# ADCS_breakout_Board_FinalVesion.net
KiCad netlist of a schematic drawn in Altium Designer
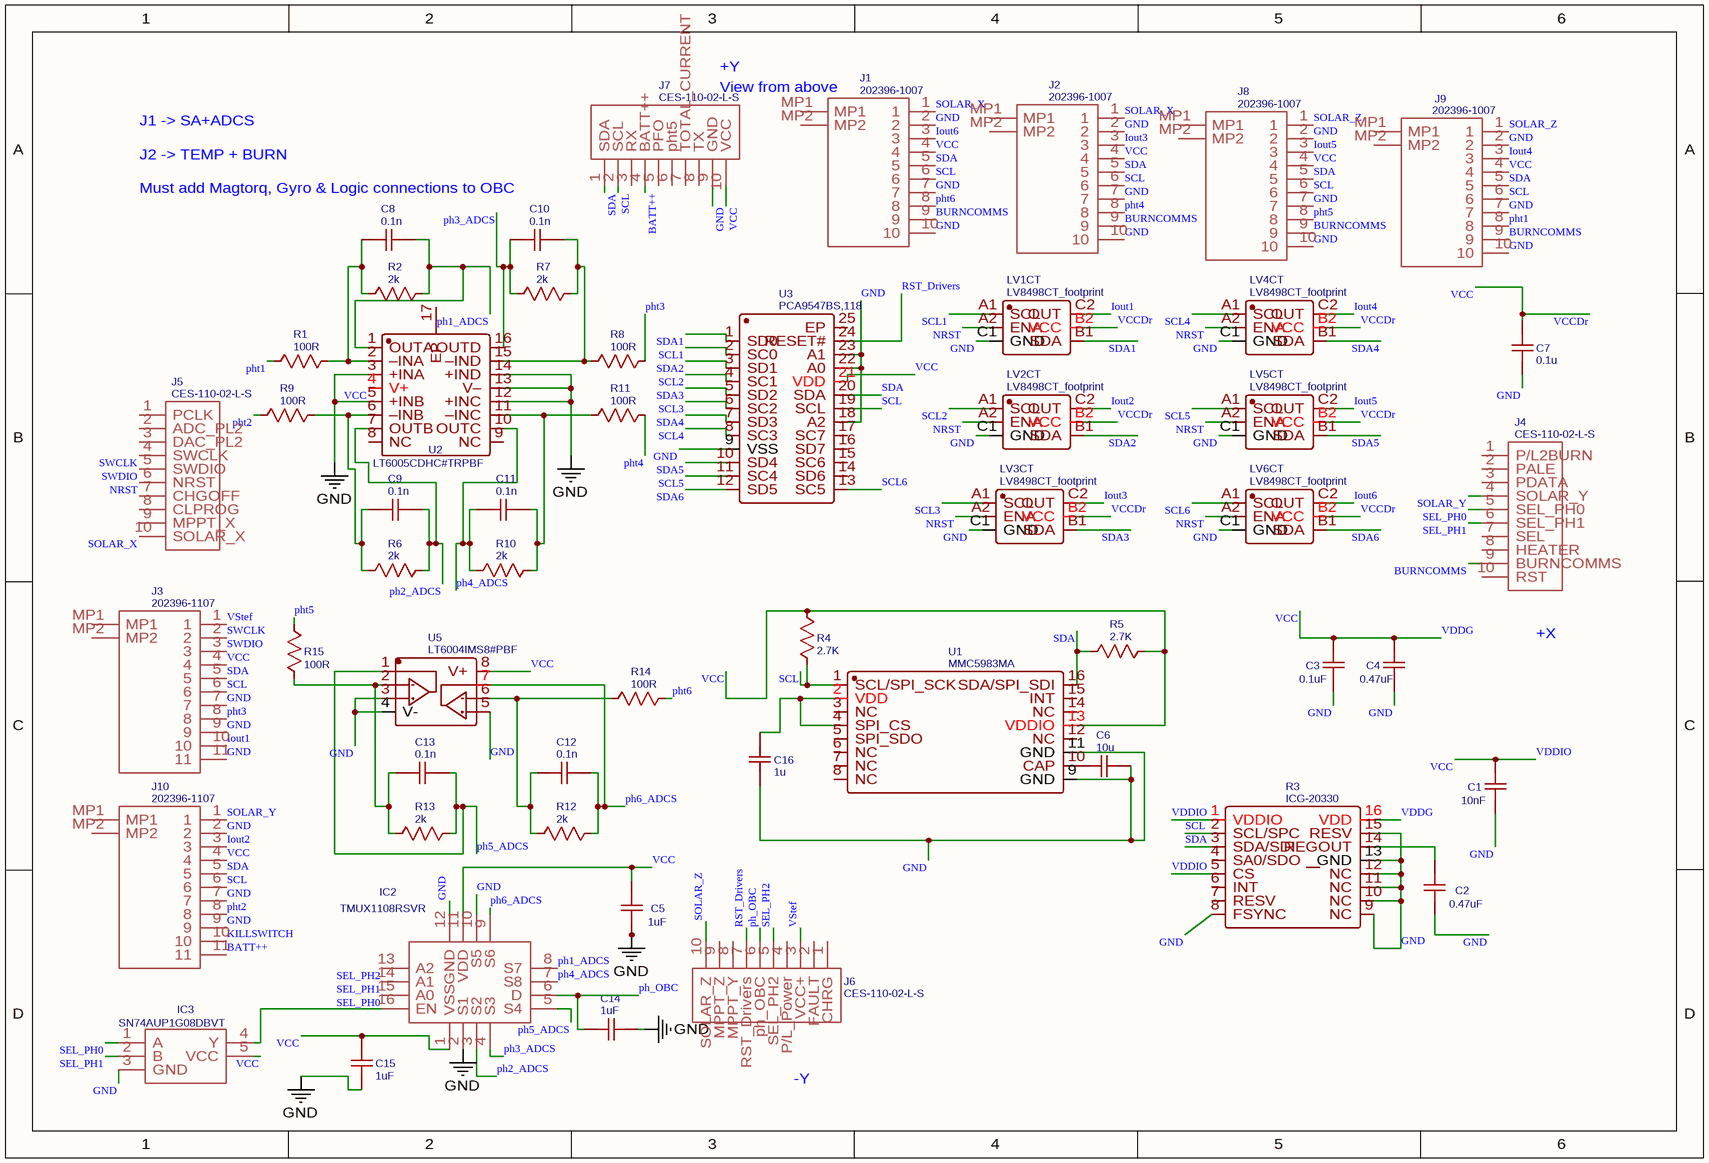
[diagram p0: ADCS&breakout_Board FinalVesion.schdoc]

(export (version "E")
  (design (tool "Eeschema 10.0.6"))
  (components
    (comp (ref "C1")
      (value "10nF")
      (footprint "C0603")
      (fields (field (name "CONTRIBUTOR") "LCEDA_Lib"))
      (libsource (lib "altium-import") (part "root_1_10nF_"))
    )
    (comp (ref "C2")
      (value "0.47uF")
      (footprint "C0603")
      (fields (field (name "CONTRIBUTOR") "LCEDA_Lib"))
      (libsource (lib "altium-import") (part "root_1_0.47uF_"))
    )
    (comp (ref "C3")
      (value "0.1uF")
      (footprint "C0603")
      (fields (field (name "CONTRIBUTOR") "LCEDA_Lib"))
      (libsource (lib "altium-import") (part "root_1_0.1uF_"))
    )
    (comp (ref "C4")
      (value "0.47uF")
      (footprint "C0603")
      (fields (field (name "CONTRIBUTOR") "LCEDA_Lib"))
      (libsource (lib "altium-import") (part "root_1_0.47uF_"))
    )
    (comp (ref "C5")
      (value "1uF")
      (footprint "C0603")
      (fields (field (name "CONTRIBUTOR") "LCEDA_Lib"))
      (libsource (lib "altium-import") (part "root_1_1uF_"))
    )
    (comp (ref "C6")
      (value "10u")
      (footprint "C0603")
      (fields (field (name "CONTRIBUTOR") "LCEDA_Lib"))
      (libsource (lib "altium-import") (part "root_0_10u_"))
    )
    (comp (ref "C7")
      (value "0.1u")
      (footprint "C0603")
      (fields (field (name "CONTRIBUTOR") "LCEDA_Lib"))
      (libsource (lib "altium-import") (part "root_3_0.1u_"))
    )
    (comp (ref "C8")
      (value "0.1n")
      (footprint "C0603")
      (fields (field (name "CONTRIBUTOR") "LCEDA_Lib"))
      (libsource (lib "altium-import") (part "root_0_0.1n_"))
    )
    (comp (ref "C9")
      (value "0.1n")
      (footprint "C0603")
      (fields (field (name "CONTRIBUTOR") "LCEDA_Lib"))
      (libsource (lib "altium-import") (part "root_0_0.1n_"))
    )
    (comp (ref "C10")
      (value "0.1n")
      (footprint "C0603")
      (fields (field (name "CONTRIBUTOR") "LCEDA_Lib"))
      (libsource (lib "altium-import") (part "root_0_0.1n_"))
    )
    (comp (ref "C11")
      (value "0.1n")
      (footprint "C0603")
      (fields (field (name "CONTRIBUTOR") "LCEDA_Lib"))
      (libsource (lib "altium-import") (part "root_0_0.1n_"))
    )
    (comp (ref "C12")
      (value "0.1n")
      (footprint "C0603")
      (fields (field (name "CONTRIBUTOR") "LCEDA_Lib"))
      (libsource (lib "altium-import") (part "root_0_0.1n_"))
    )
    (comp (ref "C13")
      (value "0.1n")
      (footprint "C0603")
      (fields (field (name "CONTRIBUTOR") "LCEDA_Lib"))
      (libsource (lib "altium-import") (part "root_0_0.1n_"))
    )
    (comp (ref "C14")
      (value "1uF")
      (footprint "C0603")
      (fields (field (name "CONTRIBUTOR") "LCEDA_Lib"))
      (libsource (lib "altium-import") (part "root_0_1uF_"))
    )
    (comp (ref "C15")
      (value "1uF")
      (footprint "C0603")
      (fields (field (name "CONTRIBUTOR") "LCEDA_Lib"))
      (libsource (lib "altium-import") (part "root_3_1uF_"))
    )
    (comp (ref "C16")
      (value "1u")
      (footprint "C0603")
      (fields (field (name "CONTRIBUTOR") "LCEDA_Lib"))
      (libsource (lib "altium-import") (part "root_3_1u_"))
    )
    (comp (ref "IC2")
      (value "TMUX1108RSVR")
      (footprint "QFN40P180X260X55-16N")
      (fields (field (name "CONTRIBUTOR") "Pol Gimenez"))
      (libsource (lib "altium-import") (part "root_1_TMUX1108RSVR_"))
    )
    (comp (ref "IC3")
      (value "SN74AUP1G08DBVT")
      (footprint "SOT95P280X145-5N")
      (fields (field (name "CONTRIBUTOR") "Pol Gimenez"))
      (libsource (lib "altium-import") (part "root_0_SN74AUP1G08DBVT_"))
    )
    (comp (ref "J1")
      (value "202396-1007")
      (footprint "2023961007")
      (fields (field (name "CONTRIBUTOR") "Pol Gimenez"))
      (libsource (lib "altium-import") (part "root_0_202396-1007_"))
    )
    (comp (ref "J2")
      (value "202396-1007")
      (footprint "2023961007")
      (fields (field (name "CONTRIBUTOR") "Pol Gimenez"))
      (libsource (lib "altium-import") (part "root_0_202396-1007_"))
    )
    (comp (ref "J3")
      (value "202396-1107")
      (footprint "2023961107")
      (fields (field (name "CONTRIBUTOR") "Pol Gimenez"))
      (libsource (lib "altium-import") (part "root_0_202396-1107_"))
    )
    (comp (ref "J4")
      (value "CES-110-02-L-S")
      (footprint "CES-110-XX-Y-S")
      (fields (field (name "CONTRIBUTOR") "George-vlad Enache"))
      (libsource (lib "altium-import") (part "root_0_CES-110-02-L-S_"))
    )
    (comp (ref "J5")
      (value "CES-110-02-L-S")
      (footprint "CES-110-XX-Y-S")
      (fields (field (name "CONTRIBUTOR") "George-vlad Enache"))
      (libsource (lib "altium-import") (part "root_0_CES-110-02-L-S_"))
    )
    (comp (ref "J6")
      (value "CES-110-02-L-S")
      (footprint "CES-110-XX-Y-S")
      (fields (field (name "CONTRIBUTOR") "George-vlad Enache"))
      (libsource (lib "altium-import") (part "root_3_CES-110-02-L-S_"))
    )
    (comp (ref "J7")
      (value "CES-110-02-L-S")
      (footprint "CES-110-XX-Y-S")
      (fields (field (name "CONTRIBUTOR") "George-vlad Enache"))
      (libsource (lib "altium-import") (part "root_1_CES-110-02-L-S_"))
    )
    (comp (ref "J8")
      (value "202396-1007")
      (footprint "2023961007")
      (fields (field (name "CONTRIBUTOR") "Pol Gimenez"))
      (libsource (lib "altium-import") (part "root_0_202396-1007_"))
    )
    (comp (ref "J9")
      (value "202396-1007")
      (footprint "2023961007")
      (fields (field (name "CONTRIBUTOR") "Pol Gimenez"))
      (libsource (lib "altium-import") (part "root_0_202396-1007_"))
    )
    (comp (ref "J10")
      (value "202396-1107")
      (footprint "2023961107")
      (fields (field (name "CONTRIBUTOR") "Pol Gimenez"))
      (libsource (lib "altium-import") (part "root_0_202396-1107_"))
    )
    (comp (ref "LV1CT")
      (value "LV8498CT_footprint")
      (footprint "WLP-6_L1.30-W0.90-P0.40-TL")
      (fields
        (field (name "BOM_MANUFACTURER PART") "LV8498CT-TE-L-H")
        (field (name "BOM_SUPPLIER PART") "863-LV8498CT-TE-L-H")
        (field (name "CONTRIBUTOR") "Miguel Diaz Montiel")
      )
      (libsource (lib "altium-import") (part "root_0_LV8498CT_footprint_"))
    )
    (comp (ref "LV2CT")
      (value "LV8498CT_footprint")
      (footprint "WLP-6_L1.30-W0.90-P0.40-TL")
      (fields
        (field (name "BOM_MANUFACTURER PART") "LV8498CT-TE-L-H")
        (field (name "BOM_SUPPLIER PART") "863-LV8498CT-TE-L-H")
        (field (name "CONTRIBUTOR") "Miguel Diaz Montiel")
      )
      (libsource (lib "altium-import") (part "root_0_LV8498CT_footprint_"))
    )
    (comp (ref "LV3CT")
      (value "LV8498CT_footprint")
      (footprint "WLP-6_L1.30-W0.90-P0.40-TL")
      (fields
        (field (name "BOM_MANUFACTURER PART") "LV8498CT-TE-L-H")
        (field (name "BOM_SUPPLIER PART") "863-LV8498CT-TE-L-H")
        (field (name "CONTRIBUTOR") "Miguel Diaz Montiel")
      )
      (libsource (lib "altium-import") (part "root_0_LV8498CT_footprint_"))
    )
    (comp (ref "LV4CT")
      (value "LV8498CT_footprint")
      (footprint "WLP-6_L1.30-W0.90-P0.40-TL")
      (fields
        (field (name "BOM_MANUFACTURER PART") "LV8498CT-TE-L-H")
        (field (name "BOM_SUPPLIER PART") "863-LV8498CT-TE-L-H")
        (field (name "CONTRIBUTOR") "Miguel Diaz Montiel")
      )
      (libsource (lib "altium-import") (part "root_0_LV8498CT_footprint_"))
    )
    (comp (ref "LV5CT")
      (value "LV8498CT_footprint")
      (footprint "WLP-6_L1.30-W0.90-P0.40-TL")
      (fields
        (field (name "BOM_MANUFACTURER PART") "LV8498CT-TE-L-H")
        (field (name "BOM_SUPPLIER PART") "863-LV8498CT-TE-L-H")
        (field (name "CONTRIBUTOR") "Miguel Diaz Montiel")
      )
      (libsource (lib "altium-import") (part "root_0_LV8498CT_footprint_"))
    )
    (comp (ref "LV6CT")
      (value "LV8498CT_footprint")
      (footprint "WLP-6_L1.30-W0.90-P0.40-TL")
      (fields
        (field (name "BOM_MANUFACTURER PART") "LV8498CT-TE-L-H")
        (field (name "BOM_SUPPLIER PART") "863-LV8498CT-TE-L-H")
        (field (name "CONTRIBUTOR") "Miguel Diaz Montiel")
      )
      (libsource (lib "altium-import") (part "root_0_LV8498CT_footprint_"))
    )
    (comp (ref "R1")
      (value "100R")
      (footprint "R0603")
      (fields (field (name "CONTRIBUTOR") "LCEDA_Lib"))
      (libsource (lib "altium-import") (part "root_0_100R_"))
    )
    (comp (ref "R2")
      (value "2k")
      (footprint "R0603")
      (fields (field (name "CONTRIBUTOR") "LCEDA_Lib"))
      (libsource (lib "altium-import") (part "root_2_2k_"))
    )
    (comp (ref "R3")
      (value "ICG-20330")
      (footprint "LGA-16_L3.0-W3.0-P0.50-BL")
      (fields (field (name "BOM_SUPPLIER PART") "C2655094") (field (name "CONTRIBUTOR") "LCSC"))
      (libsource (lib "altium-import") (part "root_0_ICG-20330_"))
    )
    (comp (ref "R4")
      (value "2.7K")
      (footprint "R0603")
      (fields (field (name "CONTRIBUTOR") "LCEDA_Lib"))
      (libsource (lib "altium-import") (part "root_1_2.7K_"))
    )
    (comp (ref "R5")
      (value "2.7K")
      (footprint "R0603")
      (fields (field (name "CONTRIBUTOR") "LCEDA_Lib"))
      (libsource (lib "altium-import") (part "root_2_2.7K_"))
    )
    (comp (ref "R6")
      (value "2k")
      (footprint "R0603")
      (fields (field (name "CONTRIBUTOR") "LCEDA_Lib"))
      (libsource (lib "altium-import") (part "root_2_2k_"))
    )
    (comp (ref "R7")
      (value "2k")
      (footprint "R0603")
      (fields (field (name "CONTRIBUTOR") "LCEDA_Lib"))
      (libsource (lib "altium-import") (part "root_2_2k_"))
    )
    (comp (ref "R8")
      (value "100R")
      (footprint "R0603")
      (fields (field (name "CONTRIBUTOR") "LCEDA_Lib"))
      (libsource (lib "altium-import") (part "root_0_100R_"))
    )
    (comp (ref "R9")
      (value "100R")
      (footprint "R0603")
      (fields (field (name "CONTRIBUTOR") "LCEDA_Lib"))
      (libsource (lib "altium-import") (part "root_0_100R_"))
    )
    (comp (ref "R10")
      (value "2k")
      (footprint "R0603")
      (fields (field (name "CONTRIBUTOR") "LCEDA_Lib"))
      (libsource (lib "altium-import") (part "root_2_2k_"))
    )
    (comp (ref "R11")
      (value "100R")
      (footprint "R0603")
      (fields (field (name "CONTRIBUTOR") "LCEDA_Lib"))
      (libsource (lib "altium-import") (part "root_0_100R_"))
    )
    (comp (ref "R12")
      (value "2k")
      (footprint "R0603")
      (fields (field (name "CONTRIBUTOR") "LCEDA_Lib"))
      (libsource (lib "altium-import") (part "root_2_2k_"))
    )
    (comp (ref "R13")
      (value "2k")
      (footprint "R0603")
      (fields (field (name "CONTRIBUTOR") "LCEDA_Lib"))
      (libsource (lib "altium-import") (part "root_2_2k_"))
    )
    (comp (ref "R14")
      (value "100R")
      (footprint "R0603")
      (fields (field (name "CONTRIBUTOR") "LCEDA_Lib"))
      (libsource (lib "altium-import") (part "root_0_100R_"))
    )
    (comp (ref "R15")
      (value "100R")
      (footprint "R0603")
      (fields (field (name "CONTRIBUTOR") "LCEDA_Lib"))
      (libsource (lib "altium-import") (part "root_1_100R_"))
    )
    (comp (ref "U1")
      (value "MMC5983MA")
      (footprint "LGA-16_L3.0-W3.0-P0.50-BL_SQ")
      (fields (field (name "BOM_SUPPLIER PART") "C404329") (field (name "CONTRIBUTOR") "LCSC"))
      (libsource (lib "altium-import") (part "root_0_MMC5983MA_"))
    )
    (comp (ref "U2")
      (value "LT6005CDHC#TRPBF")
      (footprint "DFN-16_L5.0-W3.0-P0.50-BL-EP")
      (fields (field (name "BOM_SUPPLIER PART") "C672687") (field (name "CONTRIBUTOR") "LCSC"))
      (libsource (lib "altium-import") (part "root_0_LT6005CDHC#TRPBF_"))
    )
    (comp (ref "U3")
      (value "PCA9547BS,118")
      (footprint "HVQFN-24_L4.0-W4.0-P0.50-BL-EP2.1")
      (fields (field (name "BOM_SUPPLIER PART") "C2652947") (field (name "CONTRIBUTOR") "LCSC"))
      (libsource (lib "altium-import") (part "root_0_PCA9547BS,118_"))
    )
    (comp (ref "U5")
      (value "LT6004IMS8#PBF")
      (footprint "MOSP-8_L3.0-W3.0-P0.65-LS4.9-BL")
      (fields (field (name "BOM_SUPPLIER PART") "C117424") (field (name "CONTRIBUTOR") "LCSC"))
      (libsource (lib "altium-import") (part "root_0_LT6004IMS8#PBF_"))
    )
  )
  (nets
    (net (code "1") (name "/BATT++") (class "Default")
      (node (ref "J10") (pin "11") (pinfunction "11_11") (pintype "passive"))
      (node (ref "J7") (pin "4") (pinfunction "BATT++_4") (pintype "passive"))
    )
    (net (code "2") (name "/BURNCOMMS") (class "Default")
      (node (ref "J1") (pin "9") (pinfunction "9_9") (pintype "passive"))
      (node (ref "J2") (pin "9") (pinfunction "9_9") (pintype "passive"))
      (node (ref "J4") (pin "9") (pinfunction "MPPT_X_9") (pintype "passive"))
      (node (ref "J8") (pin "9") (pinfunction "9_9") (pintype "passive"))
      (node (ref "J9") (pin "9") (pinfunction "9_9") (pintype "passive"))
    )
    (net (code "3") (name "/Iout1") (class "Default")
      (node (ref "J3") (pin "10") (pinfunction "10_10") (pintype "passive"))
      (node (ref "LV1CT") (pin "C2") (pinfunction "OUT_C2") (pintype "passive"))
    )
    (net (code "4") (name "/Iout2") (class "Default")
      (node (ref "J10") (pin "3") (pinfunction "3_3") (pintype "passive"))
      (node (ref "LV2CT") (pin "C2") (pinfunction "OUT_C2") (pintype "passive"))
    )
    (net (code "5") (name "/Iout3") (class "Default")
      (node (ref "J2") (pin "3") (pinfunction "3_3") (pintype "passive"))
      (node (ref "LV3CT") (pin "C2") (pinfunction "OUT_C2") (pintype "passive"))
    )
    (net (code "6") (name "/Iout4") (class "Default")
      (node (ref "J9") (pin "3") (pinfunction "3_3") (pintype "passive"))
      (node (ref "LV4CT") (pin "C2") (pinfunction "OUT_C2") (pintype "passive"))
    )
    (net (code "7") (name "/Iout5") (class "Default")
      (node (ref "J8") (pin "3") (pinfunction "3_3") (pintype "passive"))
      (node (ref "LV5CT") (pin "C2") (pinfunction "OUT_C2") (pintype "passive"))
    )
    (net (code "8") (name "/Iout6") (class "Default")
      (node (ref "J1") (pin "3") (pinfunction "3_3") (pintype "passive"))
      (node (ref "LV6CT") (pin "C2") (pinfunction "OUT_C2") (pintype "passive"))
    )
    (net (code "9") (name "/KILLSWITCH") (class "Default")
      (node (ref "J10") (pin "10") (pinfunction "10_10") (pintype "passive"))
    )
    (net (code "10") (name "/NRST") (class "Default")
      (node (ref "J5") (pin "6") (pinfunction "NRST_6") (pintype "passive"))
      (node (ref "LV1CT") (pin "A2") (pinfunction "ENA_A2") (pintype "passive"))
      (node (ref "LV2CT") (pin "A2") (pinfunction "ENA_A2") (pintype "passive"))
      (node (ref "LV3CT") (pin "A2") (pinfunction "ENA_A2") (pintype "passive"))
      (node (ref "LV4CT") (pin "A2") (pinfunction "ENA_A2") (pintype "passive"))
      (node (ref "LV5CT") (pin "A2") (pinfunction "ENA_A2") (pintype "passive"))
      (node (ref "LV6CT") (pin "A2") (pinfunction "ENA_A2") (pintype "passive"))
    )
    (net (code "11") (name "/RST_Drivers") (class "Default")
      (node (ref "J6") (pin "7") (pinfunction "RST_Drivers_7") (pintype "passive"))
      (node (ref "U3") (pin "24") (pinfunction "RESET#_24") (pintype "passive"))
    )
    (net (code "12") (name "/SCL") (class "Default")
      (node (ref "J1") (pin "6") (pinfunction "6_6") (pintype "passive"))
      (node (ref "J10") (pin "6") (pinfunction "6_6") (pintype "passive"))
      (node (ref "J2") (pin "6") (pinfunction "6_6") (pintype "passive"))
      (node (ref "J3") (pin "6") (pinfunction "6_6") (pintype "passive"))
      (node (ref "J7") (pin "2") (pinfunction "SCL_2") (pintype "passive"))
      (node (ref "J8") (pin "6") (pinfunction "6_6") (pintype "passive"))
      (node (ref "J9") (pin "6") (pinfunction "6_6") (pintype "passive"))
      (node (ref "R3") (pin "2") (pinfunction "SCL/SPC_2") (pintype "passive"))
      (node (ref "R4") (pin "1") (pinfunction "1_1") (pintype "passive"))
      (node (ref "U1") (pin "1") (pinfunction "SCL/SPI_SCK_1") (pintype "passive"))
      (node (ref "U3") (pin "19") (pinfunction "SCL_19") (pintype "passive"))
    )
    (net (code "13") (name "/SCL1") (class "Default")
      (node (ref "LV1CT") (pin "A1") (pinfunction "SCL_A1") (pintype "passive"))
      (node (ref "U3") (pin "2") (pinfunction "SC0_2") (pintype "passive"))
    )
    (net (code "14") (name "/SCL2") (class "Default")
      (node (ref "LV2CT") (pin "A1") (pinfunction "SCL_A1") (pintype "passive"))
      (node (ref "U3") (pin "4") (pinfunction "SC1_4") (pintype "passive"))
    )
    (net (code "15") (name "/SCL3") (class "Default")
      (node (ref "LV3CT") (pin "A1") (pinfunction "SCL_A1") (pintype "passive"))
      (node (ref "U3") (pin "6") (pinfunction "SC2_6") (pintype "passive"))
    )
    (net (code "16") (name "/SCL4") (class "Default")
      (node (ref "LV4CT") (pin "A1") (pinfunction "SCL_A1") (pintype "passive"))
      (node (ref "U3") (pin "8") (pinfunction "SC3_8") (pintype "passive"))
    )
    (net (code "17") (name "/SCL5") (class "Default")
      (node (ref "LV5CT") (pin "A1") (pinfunction "SCL_A1") (pintype "passive"))
      (node (ref "U3") (pin "11") (pinfunction "SC4_11") (pintype "passive"))
    )
    (net (code "18") (name "/SCL6") (class "Default")
      (node (ref "LV6CT") (pin "A1") (pinfunction "SCL_A1") (pintype "passive"))
      (node (ref "U3") (pin "13") (pinfunction "SC5_13") (pintype "passive"))
    )
    (net (code "19") (name "/SDA") (class "Default")
      (node (ref "J1") (pin "5") (pinfunction "5_5") (pintype "passive"))
      (node (ref "J10") (pin "5") (pinfunction "5_5") (pintype "passive"))
      (node (ref "J2") (pin "5") (pinfunction "5_5") (pintype "passive"))
      (node (ref "J3") (pin "5") (pinfunction "5_5") (pintype "passive"))
      (node (ref "J7") (pin "1") (pinfunction "SDA_1") (pintype "passive"))
      (node (ref "J8") (pin "5") (pinfunction "5_5") (pintype "passive"))
      (node (ref "J9") (pin "5") (pinfunction "5_5") (pintype "passive"))
      (node (ref "R3") (pin "3") (pinfunction "SDA/SDI_3") (pintype "passive"))
      (node (ref "R5") (pin "2") (pinfunction "2_2") (pintype "passive"))
      (node (ref "U1") (pin "16") (pinfunction "SDA/SPI_SDI_16") (pintype "passive"))
      (node (ref "U3") (pin "20") (pinfunction "SDA_20") (pintype "passive"))
    )
    (net (code "20") (name "/SDA1") (class "Default")
      (node (ref "LV1CT") (pin "B1") (pinfunction "SDA_B1") (pintype "passive"))
      (node (ref "U3") (pin "1") (pinfunction "SD0_1") (pintype "passive"))
    )
    (net (code "21") (name "/SDA2") (class "Default")
      (node (ref "LV2CT") (pin "B1") (pinfunction "SDA_B1") (pintype "passive"))
      (node (ref "U3") (pin "3") (pinfunction "SD1_3") (pintype "passive"))
    )
    (net (code "22") (name "/SDA3") (class "Default")
      (node (ref "LV3CT") (pin "B1") (pinfunction "SDA_B1") (pintype "passive"))
      (node (ref "U3") (pin "5") (pinfunction "SD2_5") (pintype "passive"))
    )
    (net (code "23") (name "/SDA4") (class "Default")
      (node (ref "LV4CT") (pin "B1") (pinfunction "SDA_B1") (pintype "passive"))
      (node (ref "U3") (pin "7") (pinfunction "SD3_7") (pintype "passive"))
    )
    (net (code "24") (name "/SDA5") (class "Default")
      (node (ref "LV5CT") (pin "B1") (pinfunction "SDA_B1") (pintype "passive"))
      (node (ref "U3") (pin "10") (pinfunction "SD4_10") (pintype "passive"))
    )
    (net (code "25") (name "/SDA6") (class "Default")
      (node (ref "LV6CT") (pin "B1") (pinfunction "SDA_B1") (pintype "passive"))
      (node (ref "U3") (pin "12") (pinfunction "SD5_12") (pintype "passive"))
    )
    (net (code "26") (name "/SEL_PH0") (class "Default")
      (node (ref "IC2") (pin "15") (pinfunction "A0_15") (pintype "passive"))
      (node (ref "IC3") (pin "1") (pinfunction "A_1") (pintype "passive"))
      (node (ref "J4") (pin "5") (pinfunction "SWDIO_5") (pintype "passive"))
    )
    (net (code "27") (name "/SEL_PH1") (class "Default")
      (node (ref "IC2") (pin "14") (pinfunction "A1_14") (pintype "passive"))
      (node (ref "IC3") (pin "2") (pinfunction "B_2") (pintype "passive"))
      (node (ref "J4") (pin "6") (pinfunction "NRST_6") (pintype "passive"))
    )
    (net (code "28") (name "/SEL_PH2") (class "Default")
      (node (ref "IC2") (pin "13") (pinfunction "A2_13") (pintype "passive"))
      (node (ref "J6") (pin "5") (pinfunction "SEL_PH2_5") (pintype "passive"))
    )
    (net (code "29") (name "/SOLAR_X") (class "Default")
      (node (ref "J1") (pin "1") (pinfunction "1_1") (pintype "passive"))
      (node (ref "J2") (pin "1") (pinfunction "1_1") (pintype "passive"))
      (node (ref "J5") (pin "10") (pinfunction "SOLAR_X_10") (pintype "passive"))
    )
    (net (code "30") (name "/SOLAR_Y") (class "Default")
      (node (ref "J10") (pin "1") (pinfunction "1_1") (pintype "passive"))
      (node (ref "J4") (pin "4") (pinfunction "SWCLK_4") (pintype "passive"))
    )
    (net (code "31") (name "/SOLAR_Z") (class "Default")
      (node (ref "J6") (pin "10") (pinfunction "SOLAR_Z_10") (pintype "passive"))
      (node (ref "J8") (pin "1") (pinfunction "1_1") (pintype "passive"))
      (node (ref "J9") (pin "1") (pinfunction "1_1") (pintype "passive"))
    )
    (net (code "32") (name "/SWCLK") (class "Default")
      (node (ref "J3") (pin "2") (pinfunction "2_2") (pintype "passive"))
      (node (ref "J5") (pin "4") (pinfunction "SWCLK_4") (pintype "passive"))
    )
    (net (code "33") (name "/SWDIO") (class "Default")
      (node (ref "J3") (pin "3") (pinfunction "3_3") (pintype "passive"))
      (node (ref "J5") (pin "5") (pinfunction "SWDIO_5") (pintype "passive"))
    )
    (net (code "34") (name "/VCC") (class "Default")
      (node (ref "C1") (pin "2") (pinfunction "2_2") (pintype "passive"))
      (node (ref "C15") (pin "1") (pinfunction "1_1") (pintype "passive"))
      (node (ref "C3") (pin "2") (pinfunction "2_2") (pintype "passive"))
      (node (ref "C4") (pin "2") (pinfunction "2_2") (pintype "passive"))
      (node (ref "C5") (pin "2") (pinfunction "2_2") (pintype "passive"))
      (node (ref "C7") (pin "1") (pinfunction "1_1") (pintype "passive"))
      (node (ref "IC2") (pin "1") (pinfunction "VSS_1") (pintype "passive"))
      (node (ref "IC2") (pin "11") (pinfunction "VDD_11") (pintype "passive"))
      (node (ref "IC3") (pin "5") (pinfunction "VCC_5") (pintype "passive"))
      (node (ref "J1") (pin "4") (pinfunction "4_4") (pintype "passive"))
      (node (ref "J10") (pin "4") (pinfunction "4_4") (pintype "passive"))
      (node (ref "J2") (pin "4") (pinfunction "4_4") (pintype "passive"))
      (node (ref "J3") (pin "4") (pinfunction "4_4") (pintype "passive"))
      (node (ref "J7") (pin "10") (pinfunction "VCC_10") (pintype "passive"))
      (node (ref "J8") (pin "4") (pinfunction "4_4") (pintype "passive"))
      (node (ref "J9") (pin "4") (pinfunction "4_4") (pintype "passive"))
      (node (ref "LV1CT") (pin "B2") (pinfunction "VCC_B2") (pintype "passive"))
      (node (ref "LV2CT") (pin "B2") (pinfunction "VCC_B2") (pintype "passive"))
      (node (ref "LV3CT") (pin "B2") (pinfunction "VCC_B2") (pintype "passive"))
      (node (ref "LV4CT") (pin "B2") (pinfunction "VCC_B2") (pintype "passive"))
      (node (ref "LV5CT") (pin "B2") (pinfunction "VCC_B2") (pintype "passive"))
      (node (ref "LV6CT") (pin "B2") (pinfunction "VCC_B2") (pintype "passive"))
      (node (ref "R3") (pin "1") (pinfunction "VDDIO_1") (pintype "passive"))
      (node (ref "R3") (pin "16") (pinfunction "VDD_16") (pintype "passive"))
      (node (ref "R3") (pin "5") (pinfunction "CS_5") (pintype "passive"))
      (node (ref "R4") (pin "2") (pinfunction "2_2") (pintype "passive"))
      (node (ref "R5") (pin "1") (pinfunction "1_1") (pintype "passive"))
      (node (ref "U1") (pin "13") (pinfunction "VDDIO_13") (pintype "passive"))
      (node (ref "U2") (pin "4") (pinfunction "V+_4") (pintype "passive"))
      (node (ref "U3") (pin "21") (pinfunction "VDD_21") (pintype "passive"))
      (node (ref "U5") (pin "8") (pinfunction "V+_8") (pintype "passive"))
    )
    (net (code "35") (name "/VStef") (class "Default")
      (node (ref "J3") (pin "1") (pinfunction "1_1") (pintype "passive"))
      (node (ref "J6") (pin "3") (pinfunction "VCC+_3") (pintype "passive"))
    )
    (net (code "36") (name "/ph1_ADCS") (class "Default")
      (node (ref "C8") (pin "2") (pinfunction "2_2") (pintype "passive"))
      (node (ref "IC2") (pin "8") (pinfunction "S7_8") (pintype "passive"))
      (node (ref "R2") (pin "1") (pinfunction "1_1") (pintype "passive"))
      (node (ref "U2") (pin "1") (pinfunction "OUTA_1") (pintype "passive"))
    )
    (net (code "37") (name "/ph2_ADCS") (class "Default")
      (node (ref "C9") (pin "2") (pinfunction "2_2") (pintype "passive"))
      (node (ref "IC2") (pin "3") (pinfunction "S2_3") (pintype "passive"))
      (node (ref "R6") (pin "1") (pinfunction "1_1") (pintype "passive"))
      (node (ref "U2") (pin "7") (pinfunction "OUTB_7") (pintype "passive"))
    )
    (net (code "38") (name "/ph3_ADCS") (class "Default")
      (node (ref "C10") (pin "1") (pinfunction "1_1") (pintype "passive"))
      (node (ref "IC2") (pin "4") (pinfunction "S3_4") (pintype "passive"))
      (node (ref "R7") (pin "2") (pinfunction "2_2") (pintype "passive"))
      (node (ref "U2") (pin "16") (pinfunction "OUTD_16") (pintype "passive"))
    )
    (net (code "39") (name "/ph4_ADCS") (class "Default")
      (node (ref "C11") (pin "1") (pinfunction "1_1") (pintype "passive"))
      (node (ref "IC2") (pin "7") (pinfunction "S8_7") (pintype "passive"))
      (node (ref "R10") (pin "2") (pinfunction "2_2") (pintype "passive"))
      (node (ref "U2") (pin "10") (pinfunction "OUTC_10") (pintype "passive"))
    )
    (net (code "40") (name "/ph5_ADCS") (class "Default")
      (node (ref "C13") (pin "2") (pinfunction "2_2") (pintype "passive"))
      (node (ref "IC2") (pin "5") (pinfunction "S4_5") (pintype "passive"))
      (node (ref "R13") (pin "1") (pinfunction "1_1") (pintype "passive"))
      (node (ref "U5") (pin "1") (pinfunction "OUTA_1") (pintype "passive"))
    )
    (net (code "41") (name "/ph6_ADCS") (class "Default")
      (node (ref "C12") (pin "2") (pinfunction "2_2") (pintype "passive"))
      (node (ref "IC2") (pin "9") (pinfunction "S6_9") (pintype "passive"))
      (node (ref "R12") (pin "1") (pinfunction "1_1") (pintype "passive"))
      (node (ref "U5") (pin "7") (pinfunction "OUTB_7") (pintype "passive"))
    )
    (net (code "42") (name "/ph_OBC") (class "Default")
      (node (ref "C14") (pin "1") (pinfunction "1_1") (pintype "passive"))
      (node (ref "IC2") (pin "6") (pinfunction "D_6") (pintype "passive"))
      (node (ref "J6") (pin "6") (pinfunction "ph_OBC_6") (pintype "passive"))
    )
    (net (code "43") (name "/pht1") (class "Default")
      (node (ref "J9") (pin "8") (pinfunction "8_8") (pintype "passive"))
      (node (ref "R1") (pin "1") (pinfunction "1_1") (pintype "passive"))
    )
    (net (code "44") (name "/pht2") (class "Default")
      (node (ref "J10") (pin "8") (pinfunction "8_8") (pintype "passive"))
      (node (ref "R9") (pin "1") (pinfunction "1_1") (pintype "passive"))
    )
    (net (code "45") (name "/pht3") (class "Default")
      (node (ref "J3") (pin "8") (pinfunction "8_8") (pintype "passive"))
      (node (ref "R8") (pin "2") (pinfunction "2_2") (pintype "passive"))
    )
    (net (code "46") (name "/pht4") (class "Default")
      (node (ref "J2") (pin "8") (pinfunction "8_8") (pintype "passive"))
      (node (ref "R11") (pin "2") (pinfunction "2_2") (pintype "passive"))
    )
    (net (code "47") (name "/pht5") (class "Default")
      (node (ref "J8") (pin "8") (pinfunction "8_8") (pintype "passive"))
      (node (ref "R15") (pin "2") (pinfunction "2_2") (pintype "passive"))
    )
    (net (code "48") (name "/pht6") (class "Default")
      (node (ref "J1") (pin "8") (pinfunction "8_8") (pintype "passive"))
      (node (ref "R14") (pin "2") (pinfunction "2_2") (pintype "passive"))
    )
    (net (code "49") (name "GND") (class "Default")
      (node (ref "C1") (pin "1") (pinfunction "1_1") (pintype "passive"))
      (node (ref "C14") (pin "2") (pinfunction "2_2") (pintype "passive"))
      (node (ref "C15") (pin "2") (pinfunction "2_2") (pintype "passive"))
      (node (ref "C16") (pin "2") (pinfunction "2_2") (pintype "passive"))
      (node (ref "C2") (pin "1") (pinfunction "1_1") (pintype "passive"))
      (node (ref "C3") (pin "1") (pinfunction "1_1") (pintype "passive"))
      (node (ref "C4") (pin "1") (pinfunction "1_1") (pintype "passive"))
      (node (ref "C5") (pin "1") (pinfunction "1_1") (pintype "passive"))
      (node (ref "C6") (pin "2") (pinfunction "2_2") (pintype "passive"))
      (node (ref "C7") (pin "2") (pinfunction "2_2") (pintype "passive"))
      (node (ref "IC2") (pin "10") (pinfunction "S5_10") (pintype "passive"))
      (node (ref "IC2") (pin "12") (pinfunction "GND_12") (pintype "passive"))
      (node (ref "IC2") (pin "2") (pinfunction "S1_2") (pintype "passive"))
      (node (ref "IC3") (pin "3") (pinfunction "GND_3") (pintype "passive"))
      (node (ref "J1") (pin "10") (pinfunction "10_10") (pintype "passive"))
      (node (ref "J1") (pin "2") (pinfunction "2_2") (pintype "passive"))
      (node (ref "J1") (pin "7") (pinfunction "7_7") (pintype "passive"))
      (node (ref "J10") (pin "2") (pinfunction "2_2") (pintype "passive"))
      (node (ref "J10") (pin "7") (pinfunction "7_7") (pintype "passive"))
      (node (ref "J10") (pin "9") (pinfunction "9_9") (pintype "passive"))
      (node (ref "J2") (pin "10") (pinfunction "10_10") (pintype "passive"))
      (node (ref "J2") (pin "2") (pinfunction "2_2") (pintype "passive"))
      (node (ref "J2") (pin "7") (pinfunction "7_7") (pintype "passive"))
      (node (ref "J3") (pin "11") (pinfunction "11_11") (pintype "passive"))
      (node (ref "J3") (pin "7") (pinfunction "7_7") (pintype "passive"))
      (node (ref "J3") (pin "9") (pinfunction "9_9") (pintype "passive"))
      (node (ref "J7") (pin "9") (pinfunction "GND_9") (pintype "passive"))
      (node (ref "J8") (pin "10") (pinfunction "10_10") (pintype "passive"))
      (node (ref "J8") (pin "2") (pinfunction "2_2") (pintype "passive"))
      (node (ref "J8") (pin "7") (pinfunction "7_7") (pintype "passive"))
      (node (ref "J9") (pin "10") (pinfunction "10_10") (pintype "passive"))
      (node (ref "J9") (pin "2") (pinfunction "2_2") (pintype "passive"))
      (node (ref "J9") (pin "7") (pinfunction "7_7") (pintype "passive"))
      (node (ref "LV1CT") (pin "C1") (pinfunction "GND_C1") (pintype "passive"))
      (node (ref "LV2CT") (pin "C1") (pinfunction "GND_C1") (pintype "passive"))
      (node (ref "LV3CT") (pin "C1") (pinfunction "GND_C1") (pintype "passive"))
      (node (ref "LV4CT") (pin "C1") (pinfunction "GND_C1") (pintype "passive"))
      (node (ref "LV5CT") (pin "C1") (pinfunction "GND_C1") (pintype "passive"))
      (node (ref "LV6CT") (pin "C1") (pinfunction "GND_C1") (pintype "passive"))
      (node (ref "R3") (pin "10") (pinfunction "NC_10") (pintype "passive"))
      (node (ref "R3") (pin "11") (pinfunction "NC_11") (pintype "passive"))
      (node (ref "R3") (pin "12") (pinfunction "NC_12") (pintype "passive"))
      (node (ref "R3") (pin "13") (pinfunction "GND_13") (pintype "passive"))
      (node (ref "R3") (pin "15") (pinfunction "RESV_15") (pintype "passive"))
      (node (ref "R3") (pin "8") (pinfunction "FSYNC_8") (pintype "passive"))
      (node (ref "R3") (pin "9") (pinfunction "NC_9") (pintype "passive"))
      (node (ref "U1") (pin "11") (pinfunction "GND_11") (pintype "passive"))
      (node (ref "U1") (pin "9") (pinfunction "GND_9") (pintype "passive"))
      (node (ref "U2") (pin "12") (pinfunction "+INC_12") (pintype "passive"))
      (node (ref "U2") (pin "13") (pinfunction "V–_13") (pintype "passive"))
      (node (ref "U2") (pin "14") (pinfunction "+IND_14") (pintype "passive"))
      (node (ref "U2") (pin "3") (pinfunction "+INA_3") (pintype "passive"))
      (node (ref "U2") (pin "5") (pinfunction "+INB_5") (pintype "passive"))
      (node (ref "U3") (pin "18") (pinfunction "A2_18") (pintype "passive"))
      (node (ref "U3") (pin "22") (pinfunction "A0_22") (pintype "passive"))
      (node (ref "U3") (pin "23") (pinfunction "A1_23") (pintype "passive"))
      (node (ref "U3") (pin "9") (pinfunction "VSS_9") (pintype "passive"))
      (node (ref "U5") (pin "3") (pinfunction "INA+_3") (pintype "passive"))
      (node (ref "U5") (pin "4") (pinfunction "V-_4") (pintype "passive"))
      (node (ref "U5") (pin "5") (pinfunction "INB+_5") (pintype "passive"))
    )
    (net (code "50") (name "Net-(IC2-EN)") (class "Default")
      (node (ref "IC2") (pin "16") (pinfunction "EN_16") (pintype "passive"))
      (node (ref "IC3") (pin "4") (pinfunction "Y_4") (pintype "passive"))
    )
    (net (code "51") (name "Net-(R3-REGOUT)") (class "Default")
      (node (ref "C2") (pin "2") (pinfunction "2_2") (pintype "passive"))
      (node (ref "R3") (pin "14") (pinfunction "REGOUT_14") (pintype "passive"))
    )
    (net (code "52") (name "Net-(U1-CAP)") (class "Default")
      (node (ref "C6") (pin "1") (pinfunction "1_1") (pintype "passive"))
      (node (ref "U1") (pin "10") (pinfunction "CAP_10") (pintype "passive"))
    )
    (net (code "53") (name "Net-(U1-SPI_CS)") (class "Default")
      (node (ref "C16") (pin "1") (pinfunction "1_1") (pintype "passive"))
      (node (ref "U1") (pin "2") (pinfunction "VDD_2") (pintype "passive"))
      (node (ref "U1") (pin "4") (pinfunction "SPI_CS_4") (pintype "passive"))
    )
    (net (code "54") (name "Net-(U2-–INA)") (class "Default")
      (node (ref "C8") (pin "1") (pinfunction "1_1") (pintype "passive"))
      (node (ref "R1") (pin "2") (pinfunction "2_2") (pintype "passive"))
      (node (ref "R2") (pin "2") (pinfunction "2_2") (pintype "passive"))
      (node (ref "U2") (pin "2") (pinfunction "–INA_2") (pintype "passive"))
    )
    (net (code "55") (name "Net-(U2-–INB)") (class "Default")
      (node (ref "C9") (pin "1") (pinfunction "1_1") (pintype "passive"))
      (node (ref "R6") (pin "2") (pinfunction "2_2") (pintype "passive"))
      (node (ref "R9") (pin "2") (pinfunction "2_2") (pintype "passive"))
      (node (ref "U2") (pin "6") (pinfunction "–INB_6") (pintype "passive"))
    )
    (net (code "56") (name "Net-(U2-–INC)") (class "Default")
      (node (ref "C11") (pin "2") (pinfunction "2_2") (pintype "passive"))
      (node (ref "R10") (pin "1") (pinfunction "1_1") (pintype "passive"))
      (node (ref "R11") (pin "1") (pinfunction "1_1") (pintype "passive"))
      (node (ref "U2") (pin "11") (pinfunction "–INC_11") (pintype "passive"))
    )
    (net (code "57") (name "Net-(U2-–IND)") (class "Default")
      (node (ref "C10") (pin "2") (pinfunction "2_2") (pintype "passive"))
      (node (ref "R7") (pin "1") (pinfunction "1_1") (pintype "passive"))
      (node (ref "R8") (pin "1") (pinfunction "1_1") (pintype "passive"))
      (node (ref "U2") (pin "15") (pinfunction "–IND_15") (pintype "passive"))
    )
    (net (code "58") (name "Net-(U5-INA-)") (class "Default")
      (node (ref "C13") (pin "1") (pinfunction "1_1") (pintype "passive"))
      (node (ref "R13") (pin "2") (pinfunction "2_2") (pintype "passive"))
      (node (ref "R15") (pin "1") (pinfunction "1_1") (pintype "passive"))
      (node (ref "U5") (pin "2") (pinfunction "INA-_2") (pintype "passive"))
    )
    (net (code "59") (name "Net-(U5-INB-)") (class "Default")
      (node (ref "C12") (pin "1") (pinfunction "1_1") (pintype "passive"))
      (node (ref "R12") (pin "2") (pinfunction "2_2") (pintype "passive"))
      (node (ref "R14") (pin "1") (pinfunction "1_1") (pintype "passive"))
      (node (ref "U5") (pin "6") (pinfunction "INB-_6") (pintype "passive"))
    )
    (net (code "60") (name "unconnected-(J1-PadMP1)") (class "Default")
      (node (ref "J1") (pin "MP1") (pinfunction "MP1_MP1") (pintype "passive"))
    )
    (net (code "61") (name "unconnected-(J1-PadMP2)") (class "Default")
      (node (ref "J1") (pin "MP2") (pinfunction "MP2_MP2") (pintype "passive"))
    )
    (net (code "62") (name "unconnected-(J2-PadMP1)") (class "Default")
      (node (ref "J2") (pin "MP1") (pinfunction "MP1_MP1") (pintype "passive"))
    )
    (net (code "63") (name "unconnected-(J2-PadMP2)") (class "Default")
      (node (ref "J2") (pin "MP2") (pinfunction "MP2_MP2") (pintype "passive"))
    )
    (net (code "64") (name "unconnected-(J3-PadMP1)") (class "Default")
      (node (ref "J3") (pin "MP1") (pinfunction "MP1_MP1") (pintype "passive"))
    )
    (net (code "65") (name "unconnected-(J3-PadMP2)") (class "Default")
      (node (ref "J3") (pin "MP2") (pinfunction "MP2_MP2") (pintype "passive"))
    )
    (net (code "66") (name "unconnected-(J4-ADC_PL2-Pad2)") (class "Default")
      (node (ref "J4") (pin "2") (pinfunction "ADC_PL2_2") (pintype "passive"))
    )
    (net (code "67") (name "unconnected-(J4-CHGOFF-Pad7)") (class "Default")
      (node (ref "J4") (pin "7") (pinfunction "CHGOFF_7") (pintype "passive"))
    )
    (net (code "68") (name "unconnected-(J4-CLPROG-Pad8)") (class "Default")
      (node (ref "J4") (pin "8") (pinfunction "CLPROG_8") (pintype "passive"))
    )
    (net (code "69") (name "unconnected-(J4-DAC_PL2-Pad3)") (class "Default")
      (node (ref "J4") (pin "3") (pinfunction "DAC_PL2_3") (pintype "passive"))
    )
    (net (code "70") (name "unconnected-(J4-PCLK-Pad1)") (class "Default")
      (node (ref "J4") (pin "1") (pinfunction "PCLK_1") (pintype "passive"))
    )
    (net (code "71") (name "unconnected-(J4-SOLAR_X-Pad10)") (class "Default")
      (node (ref "J4") (pin "10") (pinfunction "SOLAR_X_10") (pintype "passive"))
    )
    (net (code "72") (name "unconnected-(J5-ADC_PL2-Pad2)") (class "Default")
      (node (ref "J5") (pin "2") (pinfunction "ADC_PL2_2") (pintype "passive"))
    )
    (net (code "73") (name "unconnected-(J5-CHGOFF-Pad7)") (class "Default")
      (node (ref "J5") (pin "7") (pinfunction "CHGOFF_7") (pintype "passive"))
    )
    (net (code "74") (name "unconnected-(J5-CLPROG-Pad8)") (class "Default")
      (node (ref "J5") (pin "8") (pinfunction "CLPROG_8") (pintype "passive"))
    )
    (net (code "75") (name "unconnected-(J5-DAC_PL2-Pad3)") (class "Default")
      (node (ref "J5") (pin "3") (pinfunction "DAC_PL2_3") (pintype "passive"))
    )
    (net (code "76") (name "unconnected-(J5-MPPT_X-Pad9)") (class "Default")
      (node (ref "J5") (pin "9") (pinfunction "MPPT_X_9") (pintype "passive"))
    )
    (net (code "77") (name "unconnected-(J5-PCLK-Pad1)") (class "Default")
      (node (ref "J5") (pin "1") (pinfunction "PCLK_1") (pintype "passive"))
    )
    (net (code "78") (name "unconnected-(J6-CHRG-Pad1)") (class "Default")
      (node (ref "J6") (pin "1") (pinfunction "CHRG_1") (pintype "passive"))
    )
    (net (code "79") (name "unconnected-(J6-FAULT-Pad2)") (class "Default")
      (node (ref "J6") (pin "2") (pinfunction "FAULT_2") (pintype "passive"))
    )
    (net (code "80") (name "unconnected-(J6-MPPT_Y-Pad8)") (class "Default")
      (node (ref "J6") (pin "8") (pinfunction "MPPT_Y_8") (pintype "passive"))
    )
    (net (code "81") (name "unconnected-(J6-MPPT_Z-Pad9)") (class "Default")
      (node (ref "J6") (pin "9") (pinfunction "MPPT_Z_9") (pintype "passive"))
    )
    (net (code "82") (name "unconnected-(J6-P{slash}L_Power-Pad4)") (class "Default")
      (node (ref "J6") (pin "4") (pinfunction "P/L_Power_4") (pintype "passive"))
    )
    (net (code "83") (name "unconnected-(J7-PFO-Pad5)") (class "Default")
      (node (ref "J7") (pin "5") (pinfunction "PFO_5") (pintype "passive"))
    )
    (net (code "84") (name "unconnected-(J7-RX-Pad3)") (class "Default")
      (node (ref "J7") (pin "3") (pinfunction "RX_3") (pintype "passive"))
    )
    (net (code "85") (name "unconnected-(J7-TOTAL_CURRENT-Pad7)") (class "Default")
      (node (ref "J7") (pin "7") (pinfunction "TOTAL_CURRENT_7") (pintype "passive"))
    )
    (net (code "86") (name "unconnected-(J7-TX-Pad8)") (class "Default")
      (node (ref "J7") (pin "8") (pinfunction "TX_8") (pintype "passive"))
    )
    (net (code "87") (name "unconnected-(J7-pht5-Pad6)") (class "Default")
      (node (ref "J7") (pin "6") (pinfunction "pht5_6") (pintype "passive"))
    )
    (net (code "88") (name "unconnected-(J8-PadMP1)") (class "Default")
      (node (ref "J8") (pin "MP1") (pinfunction "MP1_MP1") (pintype "passive"))
    )
    (net (code "89") (name "unconnected-(J8-PadMP2)") (class "Default")
      (node (ref "J8") (pin "MP2") (pinfunction "MP2_MP2") (pintype "passive"))
    )
    (net (code "90") (name "unconnected-(J9-PadMP1)") (class "Default")
      (node (ref "J9") (pin "MP1") (pinfunction "MP1_MP1") (pintype "passive"))
    )
    (net (code "91") (name "unconnected-(J9-PadMP2)") (class "Default")
      (node (ref "J9") (pin "MP2") (pinfunction "MP2_MP2") (pintype "passive"))
    )
    (net (code "92") (name "unconnected-(J10-PadMP1)") (class "Default")
      (node (ref "J10") (pin "MP1") (pinfunction "MP1_MP1") (pintype "passive"))
    )
    (net (code "93") (name "unconnected-(J10-PadMP2)") (class "Default")
      (node (ref "J10") (pin "MP2") (pinfunction "MP2_MP2") (pintype "passive"))
    )
    (net (code "94") (name "unconnected-(R3-INT-Pad6)") (class "Default")
      (node (ref "R3") (pin "6") (pinfunction "INT_6") (pintype "passive"))
    )
    (net (code "95") (name "unconnected-(R3-Pad2)") (class "Default")
      (node (ref "R3") (pin "2") (pinfunction "2_2") (pintype "passive"))
    )
    (net (code "96") (name "unconnected-(R3-RESV-Pad7)") (class "Default")
      (node (ref "R3") (pin "7") (pinfunction "RESV_7") (pintype "passive"))
    )
    (net (code "97") (name "unconnected-(R3-SA0{slash}SDO-Pad4)") (class "Default")
      (node (ref "R3") (pin "4") (pinfunction "SA0/SDO_4") (pintype "passive"))
    )
    (net (code "98") (name "unconnected-(U1-INT-Pad15)") (class "Default")
      (node (ref "U1") (pin "15") (pinfunction "INT_15") (pintype "passive"))
    )
    (net (code "99") (name "unconnected-(U1-NC-Pad3)") (class "Default")
      (node (ref "U1") (pin "3") (pinfunction "NC_3") (pintype "passive"))
    )
    (net (code "100") (name "unconnected-(U1-NC-Pad6)") (class "Default")
      (node (ref "U1") (pin "6") (pinfunction "NC_6") (pintype "passive"))
    )
    (net (code "101") (name "unconnected-(U1-NC-Pad7)") (class "Default")
      (node (ref "U1") (pin "7") (pinfunction "NC_7") (pintype "passive"))
    )
    (net (code "102") (name "unconnected-(U1-NC-Pad8)") (class "Default")
      (node (ref "U1") (pin "8") (pinfunction "NC_8") (pintype "passive"))
    )
    (net (code "103") (name "unconnected-(U1-NC-Pad12)") (class "Default")
      (node (ref "U1") (pin "12") (pinfunction "NC_12") (pintype "passive"))
    )
    (net (code "104") (name "unconnected-(U1-NC-Pad14)") (class "Default")
      (node (ref "U1") (pin "14") (pinfunction "NC_14") (pintype "passive"))
    )
    (net (code "105") (name "unconnected-(U1-SPI_SDO-Pad5)") (class "Default")
      (node (ref "U1") (pin "5") (pinfunction "SPI_SDO_5") (pintype "passive"))
    )
    (net (code "106") (name "unconnected-(U2-EP-Pad17)") (class "Default")
      (node (ref "U2") (pin "17") (pinfunction "EP_17") (pintype "passive"))
    )
    (net (code "107") (name "unconnected-(U2-NC-Pad8)") (class "Default")
      (node (ref "U2") (pin "8") (pinfunction "NC_8") (pintype "passive"))
    )
    (net (code "108") (name "unconnected-(U2-NC-Pad9)") (class "Default")
      (node (ref "U2") (pin "9") (pinfunction "NC_9") (pintype "passive"))
    )
    (net (code "109") (name "unconnected-(U3-EP-Pad25)") (class "Default")
      (node (ref "U3") (pin "25") (pinfunction "EP_25") (pintype "passive"))
    )
    (net (code "110") (name "unconnected-(U3-SC6-Pad15)") (class "Default")
      (node (ref "U3") (pin "15") (pinfunction "SC6_15") (pintype "passive"))
    )
    (net (code "111") (name "unconnected-(U3-SC7-Pad17)") (class "Default")
      (node (ref "U3") (pin "17") (pinfunction "SC7_17") (pintype "passive"))
    )
    (net (code "112") (name "unconnected-(U3-SD6-Pad14)") (class "Default")
      (node (ref "U3") (pin "14") (pinfunction "SD6_14") (pintype "passive"))
    )
    (net (code "113") (name "unconnected-(U3-SD7-Pad16)") (class "Default")
      (node (ref "U3") (pin "16") (pinfunction "SD7_16") (pintype "passive"))
    )
  )
)
